# VSCard.net
KiCad netlist of a schematic drawn in EAGLE
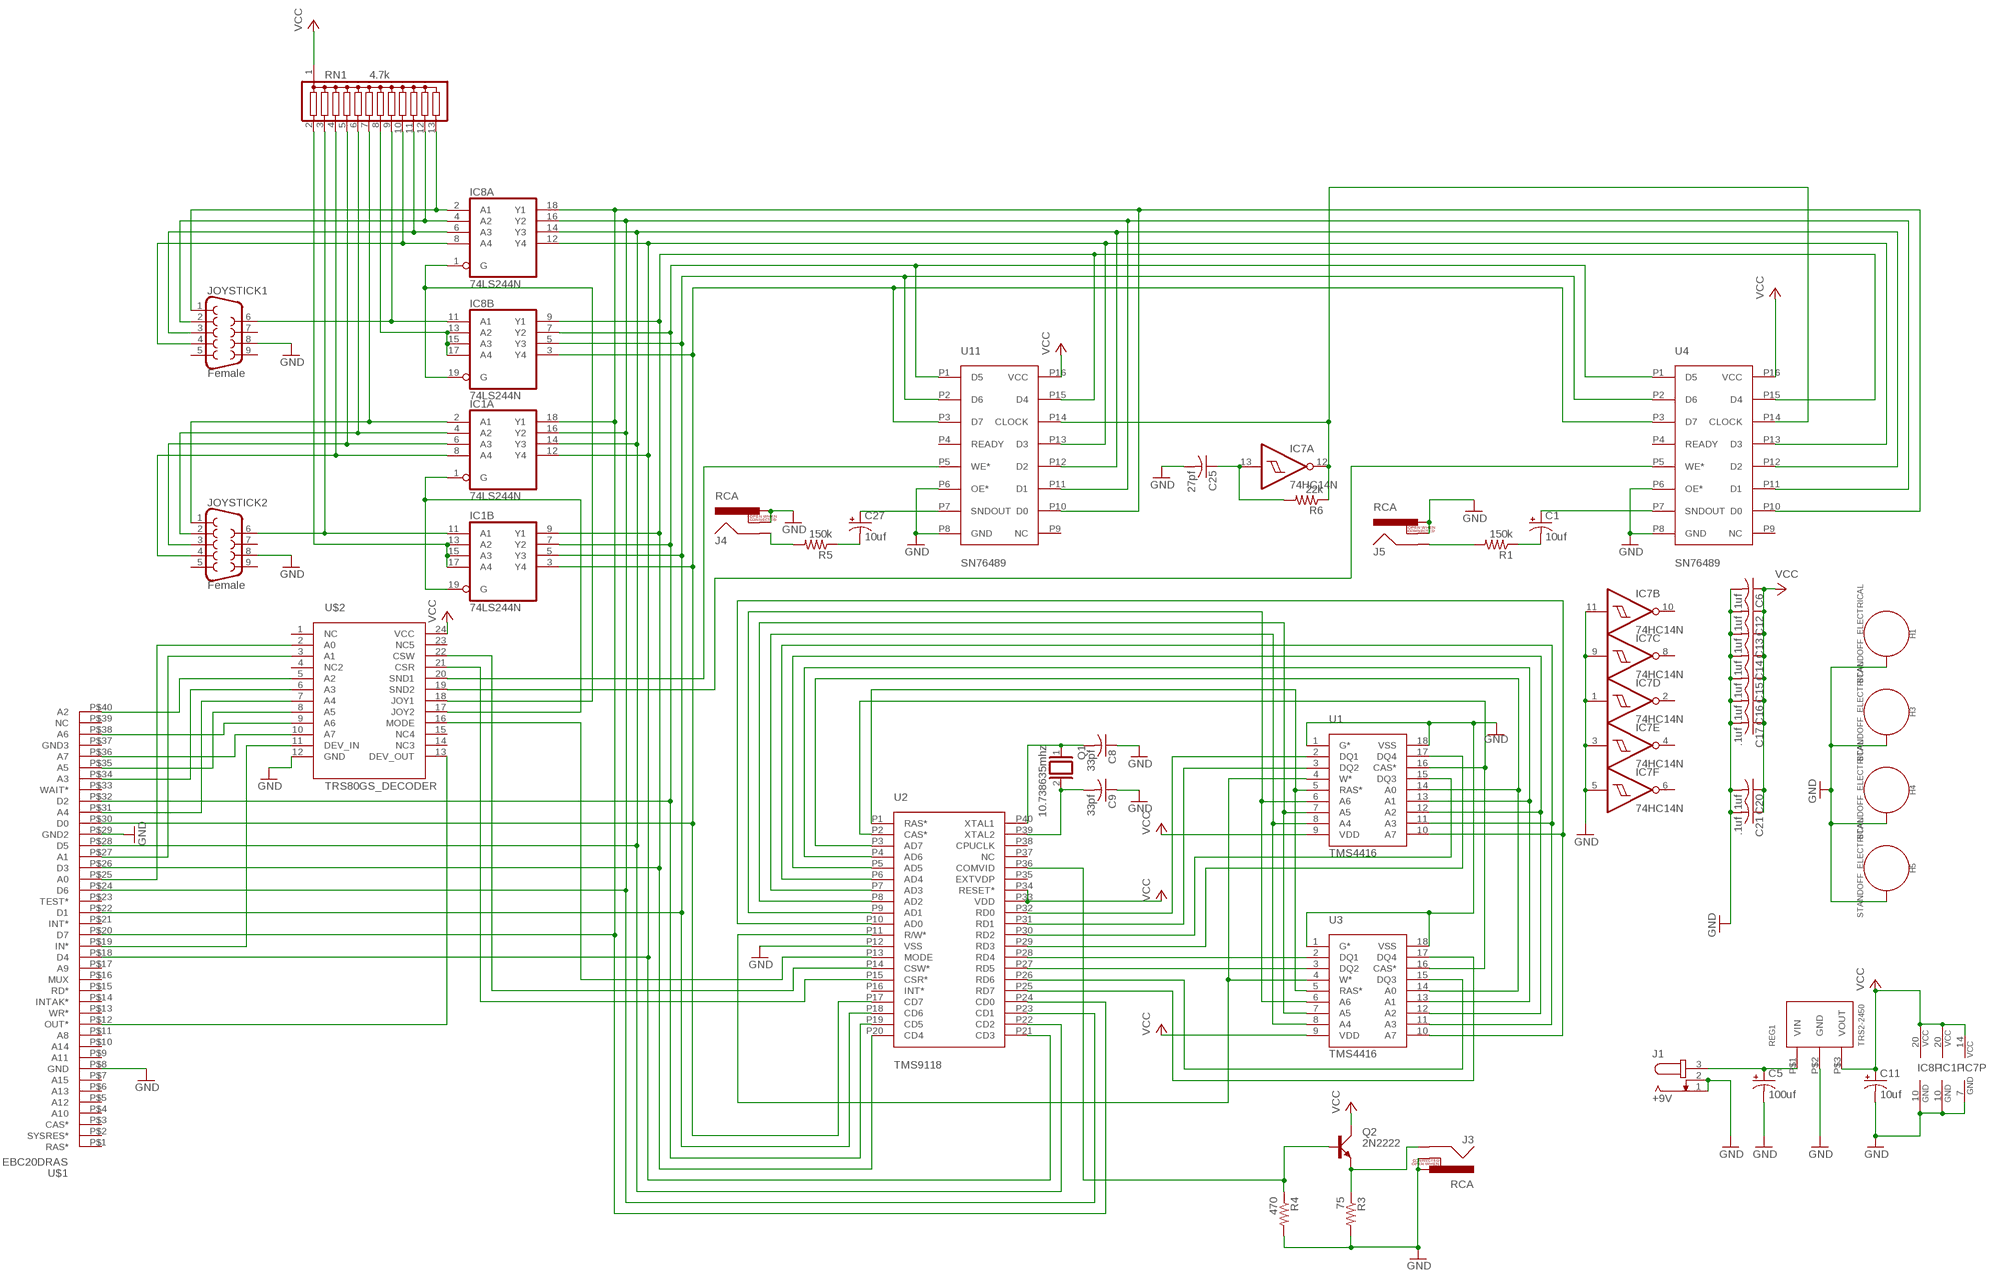
[diagram p0: schematic, sheet 1]

(export (version "E")
  (design (tool "Eeschema 10.0.6"))
  (components
    (comp (ref "C1")
      (value "10uf")
      (footprint "eagle-import:E2,5-6")
      (libsource (lib "eagle-import") (part "resistor_348_CPOL-USE2.5-6"))
    )
    (comp (ref "C5")
      (value "100uf")
      (footprint "eagle-import:E3,5-10")
      (libsource (lib "eagle-import") (part "CPOL-USE3.5-10"))
    )
    (comp (ref "C6")
      (value ".1uf")
      (footprint "eagle-import:C025-025X050")
      (libsource (lib "eagle-import") (part "resistor_348_C-US025-025X050"))
    )
    (comp (ref "C8")
      (value "33pf")
      (footprint "eagle-import:C050-050X075")
      (libsource (lib "eagle-import") (part "C-US050-050X075"))
    )
    (comp (ref "C9")
      (value "33pf")
      (footprint "eagle-import:C050-050X075")
      (libsource (lib "eagle-import") (part "C-US050-050X075"))
    )
    (comp (ref "C11")
      (value "10uf")
      (footprint "eagle-import:E3,5-10")
      (libsource (lib "eagle-import") (part "CPOL-USE3.5-10"))
    )
    (comp (ref "C12")
      (value ".1uf")
      (footprint "eagle-import:C025-025X050")
      (libsource (lib "eagle-import") (part "resistor_348_C-US025-025X050"))
    )
    (comp (ref "C13")
      (value ".1uf")
      (footprint "eagle-import:C025-025X050")
      (libsource (lib "eagle-import") (part "resistor_348_C-US025-025X050"))
    )
    (comp (ref "C14")
      (value ".1uf")
      (footprint "eagle-import:C025-025X050")
      (libsource (lib "eagle-import") (part "resistor_348_C-US025-025X050"))
    )
    (comp (ref "C15")
      (value ".1uf")
      (footprint "eagle-import:C025-025X050")
      (libsource (lib "eagle-import") (part "resistor_348_C-US025-025X050"))
    )
    (comp (ref "C16")
      (value ".1uf")
      (footprint "eagle-import:C025-025X050")
      (libsource (lib "eagle-import") (part "resistor_348_C-US025-025X050"))
    )
    (comp (ref "C17")
      (value ".1uf")
      (footprint "eagle-import:C025-025X050")
      (libsource (lib "eagle-import") (part "resistor_348_C-US025-025X050"))
    )
    (comp (ref "C20")
      (value ".1uf")
      (footprint "eagle-import:C025-025X050")
      (libsource (lib "eagle-import") (part "resistor_348_C-US025-025X050"))
    )
    (comp (ref "C21")
      (value ".1uf")
      (footprint "eagle-import:C025-025X050")
      (libsource (lib "eagle-import") (part "resistor_348_C-US025-025X050"))
    )
    (comp (ref "C25")
      (value "27pf")
      (footprint "eagle-import:C025-025X050")
      (libsource (lib "eagle-import") (part "resistor_348_C-US025-025X050"))
    )
    (comp (ref "C27")
      (value "10uf")
      (footprint "eagle-import:E2,5-6")
      (libsource (lib "eagle-import") (part "resistor_348_CPOL-USE2.5-6"))
    )
    (comp (ref "H1")
      (value "STANDOFF_ELECTRICAL")
      (footprint "eagle-import:STANDOFF-ELECTRICAL")
      (libsource (lib "eagle-import") (part "STANDOFF_ELECTRICAL"))
    )
    (comp (ref "H3")
      (value "STANDOFF_ELECTRICAL")
      (footprint "eagle-import:STANDOFF-ELECTRICAL")
      (libsource (lib "eagle-import") (part "STANDOFF_ELECTRICAL"))
    )
    (comp (ref "H4")
      (value "STANDOFF_ELECTRICAL")
      (footprint "eagle-import:STANDOFF-ELECTRICAL")
      (libsource (lib "eagle-import") (part "STANDOFF_ELECTRICAL"))
    )
    (comp (ref "H5")
      (value "STANDOFF_ELECTRICAL")
      (footprint "eagle-import:STANDOFF-ELECTRICAL")
      (libsource (lib "eagle-import") (part "STANDOFF_ELECTRICAL"))
    )
    (comp (ref "IC1")
      (value "74LS244N")
      (footprint "eagle-import:DIL20")
      (libsource (lib "eagle-import") (part "74244NLS"))
    )
    (comp (ref "IC7")
      (value "74HC14N")
      (footprint "eagle-import:DIL14")
      (libsource (lib "eagle-import") (part "7414NHC"))
    )
    (comp (ref "IC8")
      (value "74LS244N")
      (footprint "eagle-import:DIL20")
      (libsource (lib "eagle-import") (part "74244NLS"))
    )
    (comp (ref "J1")
      (value "+9V")
      (footprint "eagle-import:SPC4077")
      (libsource (lib "eagle-import") (part "JACK-PLUG0"))
    )
    (comp (ref "J3")
      (value "RCA")
      (footprint "eagle-import:RCA")
      (libsource (lib "eagle-import") (part "RCA"))
    )
    (comp (ref "J4")
      (value "RCA")
      (footprint "eagle-import:RCA")
      (libsource (lib "eagle-import") (part "RCA"))
    )
    (comp (ref "J5")
      (value "RCA")
      (footprint "eagle-import:RCA")
      (libsource (lib "eagle-import") (part "RCA"))
    )
    (comp (ref "JOYSTICK1")
      (value "Female")
      (footprint "eagle-import:DB9")
      (libsource (lib "eagle-import") (part "DB9FEMALE"))
    )
    (comp (ref "JOYSTICK2")
      (value "Female")
      (footprint "eagle-import:DB9")
      (libsource (lib "eagle-import") (part "DB9FEMALE"))
    )
    (comp (ref "Q1")
      (value "10.738635mhz")
      (footprint "eagle-import:QS")
      (libsource (lib "eagle-import") (part "XTAL/S"))
    )
    (comp (ref "Q2")
      (value "2N2222")
      (footprint "eagle-import:TO18A")
      (libsource (lib "eagle-import") (part "2N2222"))
    )
    (comp (ref "R1")
      (value "150k")
      (footprint "eagle-import:0207_2V")
      (libsource (lib "eagle-import") (part "R-US_0207/2V"))
    )
    (comp (ref "R3")
      (value "75")
      (footprint "eagle-import:0207_2V")
      (libsource (lib "eagle-import") (part "R-US_0207/2V"))
    )
    (comp (ref "R4")
      (value "470")
      (footprint "eagle-import:0207_2V")
      (libsource (lib "eagle-import") (part "R-US_0207/2V"))
    )
    (comp (ref "R5")
      (value "150k")
      (footprint "eagle-import:0207_2V")
      (libsource (lib "eagle-import") (part "R-US_0207/2V"))
    )
    (comp (ref "R6")
      (value "22k")
      (footprint "eagle-import:0207_2V")
      (libsource (lib "eagle-import") (part "R-US_0207/2V"))
    )
    (comp (ref "REG1")
      (value "TRS2-2450")
      (footprint "eagle-import:TRACON_REG")
      (libsource (lib "eagle-import") (part "TRS2-2450"))
    )
    (comp (ref "RN1")
      (value "4.7k")
      (footprint "eagle-import:SIL13")
      (libsource (lib "eagle-import") (part "G12R"))
    )
    (comp (ref "U$1")
      (value "EBC20DRAS")
      (footprint "eagle-import:EBC20DRAS")
      (libsource (lib "eagle-import") (part "EBC20DRAS"))
    )
    (comp (ref "U$2")
      (value "TRS80GS_DECODER")
      (footprint "eagle-import:DIP24SKI")
      (libsource (lib "eagle-import") (part "TRS80GS_DECODER"))
    )
    (comp (ref "U1")
      (value "TMS4416")
      (footprint "eagle-import:DIP18")
      (libsource (lib "eagle-import") (part "TMS4416"))
    )
    (comp (ref "U2")
      (value "TMS9118")
      (footprint "eagle-import:DIP40_MCU")
      (libsource (lib "eagle-import") (part "TMS9118"))
    )
    (comp (ref "U3")
      (value "TMS4416")
      (footprint "eagle-import:DIP18")
      (libsource (lib "eagle-import") (part "TMS4416"))
    )
    (comp (ref "U4")
      (value "SN76489")
      (footprint "eagle-import:DIP16")
      (libsource (lib "eagle-import") (part "SN76489"))
    )
    (comp (ref "U11")
      (value "SN76489")
      (footprint "eagle-import:DIP16")
      (libsource (lib "eagle-import") (part "SN76489"))
    )
  )
  (nets
    (net (code "1") (name "GND") (class "Default")
      (node (ref "C11") (pin "-") (pinfunction "-_-") (pintype "passive"))
      (node (ref "C12") (pin "2") (pinfunction "2_2") (pintype "passive"))
      (node (ref "C13") (pin "2") (pinfunction "2_2") (pintype "passive"))
      (node (ref "C14") (pin "2") (pinfunction "2_2") (pintype "passive"))
      (node (ref "C15") (pin "2") (pinfunction "2_2") (pintype "passive"))
      (node (ref "C16") (pin "2") (pinfunction "2_2") (pintype "passive"))
      (node (ref "C17") (pin "2") (pinfunction "2_2") (pintype "passive"))
      (node (ref "C20") (pin "2") (pinfunction "2_2") (pintype "passive"))
      (node (ref "C21") (pin "2") (pinfunction "2_2") (pintype "passive"))
      (node (ref "C25") (pin "2") (pinfunction "2_2") (pintype "passive"))
      (node (ref "C5") (pin "-") (pinfunction "-_-") (pintype "passive"))
      (node (ref "C6") (pin "2") (pinfunction "2_2") (pintype "passive"))
      (node (ref "C8") (pin "1") (pinfunction "1_1") (pintype "passive"))
      (node (ref "C9") (pin "1") (pinfunction "1_1") (pintype "passive"))
      (node (ref "H1") (pin "P1") (pinfunction "P$1_P1") (pintype "bidirectional"))
      (node (ref "H3") (pin "P1") (pinfunction "P$1_P1") (pintype "bidirectional"))
      (node (ref "H4") (pin "P1") (pinfunction "P$1_P1") (pintype "bidirectional"))
      (node (ref "H5") (pin "P1") (pinfunction "P$1_P1") (pintype "bidirectional"))
      (node (ref "IC1") (pin "10") (pinfunction "GND_10") (pintype "power_in"))
      (node (ref "IC7") (pin "1") (pinfunction "I_1") (pintype "input"))
      (node (ref "IC7") (pin "11") (pinfunction "I_11") (pintype "input"))
      (node (ref "IC7") (pin "3") (pinfunction "I_3") (pintype "input"))
      (node (ref "IC7") (pin "5") (pinfunction "I_5") (pintype "input"))
      (node (ref "IC7") (pin "7") (pinfunction "GND_7") (pintype "power_in"))
      (node (ref "IC7") (pin "9") (pinfunction "I_9") (pintype "input"))
      (node (ref "IC8") (pin "10") (pinfunction "GND_10") (pintype "power_in"))
      (node (ref "J1") (pin "1") (pinfunction "1_1") (pintype "passive"))
      (node (ref "J1") (pin "2") (pinfunction "2_2") (pintype "passive"))
      (node (ref "J3") (pin "PIN") (pinfunction "PIN_PIN") (pintype "bidirectional"))
      (node (ref "J3") (pin "SWITCH") (pinfunction "SWITCH_SWITCH") (pintype "bidirectional"))
      (node (ref "J4") (pin "PIN") (pinfunction "PIN_PIN") (pintype "bidirectional"))
      (node (ref "J4") (pin "SWITCH") (pinfunction "SWITCH_SWITCH") (pintype "bidirectional"))
      (node (ref "J5") (pin "PIN") (pinfunction "PIN_PIN") (pintype "bidirectional"))
      (node (ref "J5") (pin "SWITCH") (pinfunction "SWITCH_SWITCH") (pintype "bidirectional"))
      (node (ref "JOYSTICK1") (pin "8") (pinfunction "8_8") (pintype "passive"))
      (node (ref "JOYSTICK2") (pin "8") (pinfunction "8_8") (pintype "passive"))
      (node (ref "R3") (pin "2") (pinfunction "2_2") (pintype "passive"))
      (node (ref "R4") (pin "2") (pinfunction "2_2") (pintype "passive"))
      (node (ref "REG1") (pin "P$2") (pinfunction "GND_P$2") (pintype "bidirectional"))
      (node (ref "U$1") (pin "P$29") (pinfunction "GND2_P$29") (pintype "bidirectional"))
      (node (ref "U$1") (pin "P$8") (pinfunction "GND_P$8") (pintype "bidirectional"))
      (node (ref "U$2") (pin "12") (pinfunction "GND_12") (pintype "bidirectional"))
      (node (ref "U1") (pin "1") (pinfunction "G*_1") (pintype "bidirectional"))
      (node (ref "U1") (pin "18") (pinfunction "VSS_18") (pintype "bidirectional"))
      (node (ref "U11") (pin "P6") (pinfunction "OE*_P6") (pintype "bidirectional"))
      (node (ref "U11") (pin "P8") (pinfunction "GND_P8") (pintype "bidirectional"))
      (node (ref "U2") (pin "P12") (pinfunction "VSS_P12") (pintype "bidirectional"))
      (node (ref "U3") (pin "1") (pinfunction "G*_1") (pintype "bidirectional"))
      (node (ref "U3") (pin "18") (pinfunction "VSS_18") (pintype "bidirectional"))
      (node (ref "U4") (pin "P6") (pinfunction "OE*_P6") (pintype "bidirectional"))
      (node (ref "U4") (pin "P8") (pinfunction "GND_P8") (pintype "bidirectional"))
    )
    (net (code "2") (name "Net-(C1-Pad-)") (class "Default")
      (node (ref "C1") (pin "-") (pinfunction "-_-") (pintype "passive"))
      (node (ref "R1") (pin "1") (pinfunction "1_1") (pintype "passive"))
    )
    (net (code "3") (name "Net-(C27-Pad-)") (class "Default")
      (node (ref "C27") (pin "-") (pinfunction "-_-") (pintype "passive"))
      (node (ref "R5") (pin "1") (pinfunction "1_1") (pintype "passive"))
    )
    (net (code "4") (name "Net-(IC1A-A1)") (class "Default")
      (node (ref "IC1") (pin "2") (pinfunction "A1_2") (pintype "input"))
      (node (ref "JOYSTICK2") (pin "1") (pinfunction "1_1") (pintype "passive"))
      (node (ref "RN1") (pin "7") (pinfunction "7_7") (pintype "passive"))
    )
    (net (code "5") (name "Net-(IC1A-A2)") (class "Default")
      (node (ref "IC1") (pin "4") (pinfunction "A2_4") (pintype "input"))
      (node (ref "JOYSTICK2") (pin "2") (pinfunction "2_2") (pintype "passive"))
      (node (ref "RN1") (pin "6") (pinfunction "6_6") (pintype "passive"))
    )
    (net (code "6") (name "Net-(IC1A-A3)") (class "Default")
      (node (ref "IC1") (pin "6") (pinfunction "A3_6") (pintype "input"))
      (node (ref "JOYSTICK2") (pin "3") (pinfunction "3_3") (pintype "passive"))
      (node (ref "RN1") (pin "5") (pinfunction "5_5") (pintype "passive"))
    )
    (net (code "7") (name "Net-(IC1A-A4)") (class "Default")
      (node (ref "IC1") (pin "8") (pinfunction "A4_8") (pintype "input"))
      (node (ref "JOYSTICK2") (pin "4") (pinfunction "4_4") (pintype "passive"))
      (node (ref "RN1") (pin "4") (pinfunction "4_4") (pintype "passive"))
    )
    (net (code "8") (name "Net-(IC1A-G)") (class "Default")
      (node (ref "IC1") (pin "1") (pinfunction "G_1") (pintype "input"))
      (node (ref "IC1") (pin "19") (pinfunction "G_19") (pintype "input"))
      (node (ref "U$2") (pin "17") (pinfunction "JOY2_17") (pintype "bidirectional"))
    )
    (net (code "9") (name "Net-(IC1A-Y1)") (class "Default")
      (node (ref "IC1") (pin "18") (pinfunction "Y1_18") (pintype "tri_state"))
      (node (ref "IC8") (pin "18") (pinfunction "Y1_18") (pintype "tri_state"))
      (node (ref "U$1") (pin "P$20") (pinfunction "D7_P$20") (pintype "bidirectional"))
      (node (ref "U11") (pin "P10") (pinfunction "D0_P10") (pintype "bidirectional"))
      (node (ref "U2") (pin "P24") (pinfunction "CD0_P24") (pintype "bidirectional"))
      (node (ref "U4") (pin "P10") (pinfunction "D0_P10") (pintype "bidirectional"))
    )
    (net (code "10") (name "Net-(IC1A-Y2)") (class "Default")
      (node (ref "IC1") (pin "16") (pinfunction "Y2_16") (pintype "tri_state"))
      (node (ref "IC8") (pin "16") (pinfunction "Y2_16") (pintype "tri_state"))
      (node (ref "U$1") (pin "P$24") (pinfunction "D6_P$24") (pintype "bidirectional"))
      (node (ref "U11") (pin "P11") (pinfunction "D1_P11") (pintype "bidirectional"))
      (node (ref "U2") (pin "P23") (pinfunction "CD1_P23") (pintype "bidirectional"))
      (node (ref "U4") (pin "P11") (pinfunction "D1_P11") (pintype "bidirectional"))
    )
    (net (code "11") (name "Net-(IC1A-Y3)") (class "Default")
      (node (ref "IC1") (pin "14") (pinfunction "Y3_14") (pintype "tri_state"))
      (node (ref "IC8") (pin "14") (pinfunction "Y3_14") (pintype "tri_state"))
      (node (ref "U$1") (pin "P$28") (pinfunction "D5_P$28") (pintype "bidirectional"))
      (node (ref "U11") (pin "P12") (pinfunction "D2_P12") (pintype "bidirectional"))
      (node (ref "U2") (pin "P22") (pinfunction "CD2_P22") (pintype "bidirectional"))
      (node (ref "U4") (pin "P12") (pinfunction "D2_P12") (pintype "bidirectional"))
    )
    (net (code "12") (name "Net-(IC1A-Y4)") (class "Default")
      (node (ref "IC1") (pin "12") (pinfunction "Y4_12") (pintype "tri_state"))
      (node (ref "IC8") (pin "12") (pinfunction "Y4_12") (pintype "tri_state"))
      (node (ref "U$1") (pin "P$18") (pinfunction "D4_P$18") (pintype "bidirectional"))
      (node (ref "U11") (pin "P13") (pinfunction "D3_P13") (pintype "bidirectional"))
      (node (ref "U2") (pin "P21") (pinfunction "CD3_P21") (pintype "bidirectional"))
      (node (ref "U4") (pin "P13") (pinfunction "D3_P13") (pintype "bidirectional"))
    )
    (net (code "13") (name "Net-(IC1B-A1)") (class "Default")
      (node (ref "IC1") (pin "11") (pinfunction "A1_11") (pintype "input"))
      (node (ref "JOYSTICK2") (pin "6") (pinfunction "6_6") (pintype "passive"))
      (node (ref "RN1") (pin "3") (pinfunction "3_3") (pintype "passive"))
    )
    (net (code "14") (name "Net-(IC1B-A2)") (class "Default")
      (node (ref "IC1") (pin "13") (pinfunction "A2_13") (pintype "input"))
      (node (ref "IC1") (pin "15") (pinfunction "A3_15") (pintype "input"))
      (node (ref "IC1") (pin "17") (pinfunction "A4_17") (pintype "input"))
      (node (ref "RN1") (pin "2") (pinfunction "2_2") (pintype "passive"))
    )
    (net (code "15") (name "Net-(IC1B-Y1)") (class "Default")
      (node (ref "IC1") (pin "9") (pinfunction "Y1_9") (pintype "tri_state"))
      (node (ref "IC8") (pin "9") (pinfunction "Y1_9") (pintype "tri_state"))
      (node (ref "U$1") (pin "P$26") (pinfunction "D3_P$26") (pintype "bidirectional"))
      (node (ref "U11") (pin "P15") (pinfunction "D4_P15") (pintype "bidirectional"))
      (node (ref "U2") (pin "P20") (pinfunction "CD4_P20") (pintype "bidirectional"))
      (node (ref "U4") (pin "P15") (pinfunction "D4_P15") (pintype "bidirectional"))
    )
    (net (code "16") (name "Net-(IC1B-Y2)") (class "Default")
      (node (ref "IC1") (pin "7") (pinfunction "Y2_7") (pintype "tri_state"))
      (node (ref "IC8") (pin "7") (pinfunction "Y2_7") (pintype "tri_state"))
      (node (ref "U$1") (pin "P$32") (pinfunction "D2_P$32") (pintype "bidirectional"))
      (node (ref "U11") (pin "P1") (pinfunction "D5_P1") (pintype "bidirectional"))
      (node (ref "U2") (pin "P19") (pinfunction "CD5_P19") (pintype "bidirectional"))
      (node (ref "U4") (pin "P1") (pinfunction "D5_P1") (pintype "bidirectional"))
    )
    (net (code "17") (name "Net-(IC1B-Y3)") (class "Default")
      (node (ref "IC1") (pin "5") (pinfunction "Y3_5") (pintype "tri_state"))
      (node (ref "IC8") (pin "5") (pinfunction "Y3_5") (pintype "tri_state"))
      (node (ref "U$1") (pin "P$22") (pinfunction "D1_P$22") (pintype "bidirectional"))
      (node (ref "U11") (pin "P2") (pinfunction "D6_P2") (pintype "bidirectional"))
      (node (ref "U2") (pin "P18") (pinfunction "CD6_P18") (pintype "bidirectional"))
      (node (ref "U4") (pin "P2") (pinfunction "D6_P2") (pintype "bidirectional"))
    )
    (net (code "18") (name "Net-(IC1B-Y4)") (class "Default")
      (node (ref "IC1") (pin "3") (pinfunction "Y4_3") (pintype "tri_state"))
      (node (ref "IC8") (pin "3") (pinfunction "Y4_3") (pintype "tri_state"))
      (node (ref "U$1") (pin "P$30") (pinfunction "D0_P$30") (pintype "bidirectional"))
      (node (ref "U11") (pin "P3") (pinfunction "D7_P3") (pintype "bidirectional"))
      (node (ref "U2") (pin "P17") (pinfunction "CD7_P17") (pintype "bidirectional"))
      (node (ref "U4") (pin "P3") (pinfunction "D7_P3") (pintype "bidirectional"))
    )
    (net (code "19") (name "Net-(IC7A-I)") (class "Default")
      (node (ref "C25") (pin "1") (pinfunction "1_1") (pintype "passive"))
      (node (ref "IC7") (pin "13") (pinfunction "I_13") (pintype "input"))
      (node (ref "R6") (pin "2") (pinfunction "2_2") (pintype "passive"))
    )
    (net (code "20") (name "Net-(IC7A-O)") (class "Default")
      (node (ref "IC7") (pin "12") (pinfunction "O_12") (pintype "output"))
      (node (ref "R6") (pin "1") (pinfunction "1_1") (pintype "passive"))
      (node (ref "U11") (pin "P14") (pinfunction "CLOCK_P14") (pintype "bidirectional"))
      (node (ref "U4") (pin "P14") (pinfunction "CLOCK_P14") (pintype "bidirectional"))
    )
    (net (code "21") (name "Net-(IC8A-A1)") (class "Default")
      (node (ref "IC8") (pin "2") (pinfunction "A1_2") (pintype "input"))
      (node (ref "JOYSTICK1") (pin "1") (pinfunction "1_1") (pintype "passive"))
      (node (ref "RN1") (pin "13") (pinfunction "13_13") (pintype "passive"))
    )
    (net (code "22") (name "Net-(IC8A-A2)") (class "Default")
      (node (ref "IC8") (pin "4") (pinfunction "A2_4") (pintype "input"))
      (node (ref "JOYSTICK1") (pin "2") (pinfunction "2_2") (pintype "passive"))
      (node (ref "RN1") (pin "12") (pinfunction "12_12") (pintype "passive"))
    )
    (net (code "23") (name "Net-(IC8A-A3)") (class "Default")
      (node (ref "IC8") (pin "6") (pinfunction "A3_6") (pintype "input"))
      (node (ref "JOYSTICK1") (pin "3") (pinfunction "3_3") (pintype "passive"))
      (node (ref "RN1") (pin "11") (pinfunction "11_11") (pintype "passive"))
    )
    (net (code "24") (name "Net-(IC8A-A4)") (class "Default")
      (node (ref "IC8") (pin "8") (pinfunction "A4_8") (pintype "input"))
      (node (ref "JOYSTICK1") (pin "4") (pinfunction "4_4") (pintype "passive"))
      (node (ref "RN1") (pin "10") (pinfunction "10_10") (pintype "passive"))
    )
    (net (code "25") (name "Net-(IC8A-G)") (class "Default")
      (node (ref "IC8") (pin "1") (pinfunction "G_1") (pintype "input"))
      (node (ref "IC8") (pin "19") (pinfunction "G_19") (pintype "input"))
      (node (ref "U$2") (pin "18") (pinfunction "JOY1_18") (pintype "bidirectional"))
    )
    (net (code "26") (name "Net-(IC8B-A1)") (class "Default")
      (node (ref "IC8") (pin "11") (pinfunction "A1_11") (pintype "input"))
      (node (ref "JOYSTICK1") (pin "6") (pinfunction "6_6") (pintype "passive"))
      (node (ref "RN1") (pin "9") (pinfunction "9_9") (pintype "passive"))
    )
    (net (code "27") (name "Net-(IC8B-A2)") (class "Default")
      (node (ref "IC8") (pin "13") (pinfunction "A2_13") (pintype "input"))
      (node (ref "IC8") (pin "15") (pinfunction "A3_15") (pintype "input"))
      (node (ref "IC8") (pin "17") (pinfunction "A4_17") (pintype "input"))
      (node (ref "RN1") (pin "8") (pinfunction "8_8") (pintype "passive"))
    )
    (net (code "28") (name "Net-(J3-PadSHELL)") (class "Default")
      (node (ref "J3") (pin "SHELL") (pinfunction "SHELL_SHELL") (pintype "bidirectional"))
      (node (ref "Q2") (pin "E") (pinfunction "E_E") (pintype "passive"))
      (node (ref "R3") (pin "1") (pinfunction "1_1") (pintype "passive"))
    )
    (net (code "29") (name "Net-(J4-PadSHELL)") (class "Default")
      (node (ref "J4") (pin "SHELL") (pinfunction "SHELL_SHELL") (pintype "bidirectional"))
      (node (ref "R5") (pin "2") (pinfunction "2_2") (pintype "passive"))
    )
    (net (code "30") (name "Net-(J5-PadSHELL)") (class "Default")
      (node (ref "J5") (pin "SHELL") (pinfunction "SHELL_SHELL") (pintype "bidirectional"))
      (node (ref "R1") (pin "2") (pinfunction "2_2") (pintype "passive"))
    )
    (net (code "31") (name "Net-(REG1-VIN)") (class "Default")
      (node (ref "C5") (pin "+") (pinfunction "+_+") (pintype "passive"))
      (node (ref "J1") (pin "3") (pinfunction "3_3") (pintype "passive"))
      (node (ref "REG1") (pin "P$1") (pinfunction "VIN_P$1") (pintype "bidirectional"))
    )
    (net (code "32") (name "Net-(U$1-A0)") (class "Default")
      (node (ref "U$1") (pin "P$25") (pinfunction "A0_P$25") (pintype "bidirectional"))
      (node (ref "U$2") (pin "2") (pinfunction "A0_2") (pintype "bidirectional"))
    )
    (net (code "33") (name "Net-(U$1-A1)") (class "Default")
      (node (ref "U$1") (pin "P$27") (pinfunction "A1_P$27") (pintype "bidirectional"))
      (node (ref "U$2") (pin "3") (pinfunction "A1_3") (pintype "bidirectional"))
    )
    (net (code "34") (name "Net-(U$1-A2)") (class "Default")
      (node (ref "U$1") (pin "P$40") (pinfunction "A2_P$40") (pintype "bidirectional"))
      (node (ref "U$2") (pin "5") (pinfunction "A2_5") (pintype "bidirectional"))
    )
    (net (code "35") (name "Net-(U$1-A3)") (class "Default")
      (node (ref "U$1") (pin "P$34") (pinfunction "A3_P$34") (pintype "bidirectional"))
      (node (ref "U$2") (pin "6") (pinfunction "A3_6") (pintype "bidirectional"))
    )
    (net (code "36") (name "Net-(U$1-A4)") (class "Default")
      (node (ref "U$1") (pin "P$31") (pinfunction "A4_P$31") (pintype "bidirectional"))
      (node (ref "U$2") (pin "7") (pinfunction "A4_7") (pintype "bidirectional"))
    )
    (net (code "37") (name "Net-(U$1-A5)") (class "Default")
      (node (ref "U$1") (pin "P$35") (pinfunction "A5_P$35") (pintype "bidirectional"))
      (node (ref "U$2") (pin "8") (pinfunction "A5_8") (pintype "bidirectional"))
    )
    (net (code "38") (name "Net-(U$1-A6)") (class "Default")
      (node (ref "U$1") (pin "P$38") (pinfunction "A6_P$38") (pintype "bidirectional"))
      (node (ref "U$2") (pin "9") (pinfunction "A6_9") (pintype "bidirectional"))
    )
    (net (code "39") (name "Net-(U$1-A7)") (class "Default")
      (node (ref "U$1") (pin "P$36") (pinfunction "A7_P$36") (pintype "bidirectional"))
      (node (ref "U$2") (pin "10") (pinfunction "A7_10") (pintype "bidirectional"))
    )
    (net (code "40") (name "Net-(U$1-IN*)") (class "Default")
      (node (ref "U$1") (pin "P$19") (pinfunction "IN*_P$19") (pintype "bidirectional"))
      (node (ref "U$2") (pin "11") (pinfunction "DEV_IN_11") (pintype "bidirectional"))
    )
    (net (code "41") (name "Net-(U$1-OUT*)") (class "Default")
      (node (ref "U$1") (pin "P$12") (pinfunction "OUT*_P$12") (pintype "bidirectional"))
      (node (ref "U$2") (pin "13") (pinfunction "DEV_OUT_13") (pintype "bidirectional"))
    )
    (net (code "42") (name "Net-(U$2-CSR)") (class "Default")
      (node (ref "U$2") (pin "21") (pinfunction "CSR_21") (pintype "bidirectional"))
      (node (ref "U2") (pin "P15") (pinfunction "CSR*_P15") (pintype "bidirectional"))
    )
    (net (code "43") (name "Net-(U$2-CSW)") (class "Default")
      (node (ref "U$2") (pin "22") (pinfunction "CSW_22") (pintype "bidirectional"))
      (node (ref "U2") (pin "P14") (pinfunction "CSW*_P14") (pintype "bidirectional"))
    )
    (net (code "44") (name "Net-(U$2-MODE)") (class "Default")
      (node (ref "U$2") (pin "16") (pinfunction "MODE_16") (pintype "bidirectional"))
      (node (ref "U2") (pin "P13") (pinfunction "MODE_P13") (pintype "bidirectional"))
    )
    (net (code "45") (name "Net-(U$2-SND1)") (class "Default")
      (node (ref "U$2") (pin "20") (pinfunction "SND1_20") (pintype "bidirectional"))
      (node (ref "U11") (pin "P5") (pinfunction "WE*_P5") (pintype "bidirectional"))
    )
    (net (code "46") (name "Net-(U$2-SND2)") (class "Default")
      (node (ref "U$2") (pin "19") (pinfunction "SND2_19") (pintype "bidirectional"))
      (node (ref "U4") (pin "P5") (pinfunction "WE*_P5") (pintype "bidirectional"))
    )
    (net (code "47") (name "Net-(U1-A0)") (class "Default")
      (node (ref "U1") (pin "14") (pinfunction "A0_14") (pintype "bidirectional"))
      (node (ref "U2") (pin "P3") (pinfunction "AD7_P3") (pintype "bidirectional"))
      (node (ref "U3") (pin "14") (pinfunction "A0_14") (pintype "bidirectional"))
    )
    (net (code "48") (name "Net-(U1-A1)") (class "Default")
      (node (ref "U1") (pin "13") (pinfunction "A1_13") (pintype "bidirectional"))
      (node (ref "U2") (pin "P4") (pinfunction "AD6_P4") (pintype "bidirectional"))
      (node (ref "U3") (pin "13") (pinfunction "A1_13") (pintype "bidirectional"))
    )
    (net (code "49") (name "Net-(U1-A2)") (class "Default")
      (node (ref "U1") (pin "12") (pinfunction "A2_12") (pintype "bidirectional"))
      (node (ref "U2") (pin "P5") (pinfunction "AD5_P5") (pintype "bidirectional"))
      (node (ref "U3") (pin "12") (pinfunction "A2_12") (pintype "bidirectional"))
    )
    (net (code "50") (name "Net-(U1-A3)") (class "Default")
      (node (ref "U1") (pin "11") (pinfunction "A3_11") (pintype "bidirectional"))
      (node (ref "U2") (pin "P6") (pinfunction "AD4_P6") (pintype "bidirectional"))
      (node (ref "U3") (pin "11") (pinfunction "A3_11") (pintype "bidirectional"))
    )
    (net (code "51") (name "Net-(U1-A4)") (class "Default")
      (node (ref "U1") (pin "8") (pinfunction "A4_8") (pintype "bidirectional"))
      (node (ref "U2") (pin "P7") (pinfunction "AD3_P7") (pintype "bidirectional"))
      (node (ref "U3") (pin "8") (pinfunction "A4_8") (pintype "bidirectional"))
    )
    (net (code "52") (name "Net-(U1-A5)") (class "Default")
      (node (ref "U1") (pin "7") (pinfunction "A5_7") (pintype "bidirectional"))
      (node (ref "U2") (pin "P8") (pinfunction "AD2_P8") (pintype "bidirectional"))
      (node (ref "U3") (pin "7") (pinfunction "A5_7") (pintype "bidirectional"))
    )
    (net (code "53") (name "Net-(U1-A6)") (class "Default")
      (node (ref "U1") (pin "6") (pinfunction "A6_6") (pintype "bidirectional"))
      (node (ref "U2") (pin "P9") (pinfunction "AD1_P9") (pintype "bidirectional"))
      (node (ref "U3") (pin "6") (pinfunction "A6_6") (pintype "bidirectional"))
    )
    (net (code "54") (name "Net-(U1-A7)") (class "Default")
      (node (ref "U1") (pin "10") (pinfunction "A7_10") (pintype "bidirectional"))
      (node (ref "U2") (pin "P10") (pinfunction "AD0_P10") (pintype "bidirectional"))
      (node (ref "U3") (pin "10") (pinfunction "A7_10") (pintype "bidirectional"))
    )
    (net (code "55") (name "Net-(U1-CAS*)") (class "Default")
      (node (ref "U1") (pin "16") (pinfunction "CAS*_16") (pintype "bidirectional"))
      (node (ref "U2") (pin "P2") (pinfunction "CAS*_P2") (pintype "bidirectional"))
      (node (ref "U3") (pin "16") (pinfunction "CAS*_16") (pintype "bidirectional"))
    )
    (net (code "56") (name "Net-(U1-DQ1)") (class "Default")
      (node (ref "U1") (pin "2") (pinfunction "DQ1_2") (pintype "bidirectional"))
      (node (ref "U2") (pin "P32") (pinfunction "RD0_P32") (pintype "bidirectional"))
    )
    (net (code "57") (name "Net-(U1-DQ2)") (class "Default")
      (node (ref "U1") (pin "3") (pinfunction "DQ2_3") (pintype "bidirectional"))
      (node (ref "U2") (pin "P31") (pinfunction "RD1_P31") (pintype "bidirectional"))
    )
    (net (code "58") (name "Net-(U1-DQ3)") (class "Default")
      (node (ref "U1") (pin "15") (pinfunction "DQ3_15") (pintype "bidirectional"))
      (node (ref "U2") (pin "P30") (pinfunction "RD2_P30") (pintype "bidirectional"))
    )
    (net (code "59") (name "Net-(U1-DQ4)") (class "Default")
      (node (ref "U1") (pin "17") (pinfunction "DQ4_17") (pintype "bidirectional"))
      (node (ref "U2") (pin "P29") (pinfunction "RD3_P29") (pintype "bidirectional"))
    )
    (net (code "60") (name "Net-(U1-RAS*)") (class "Default")
      (node (ref "U1") (pin "5") (pinfunction "RAS*_5") (pintype "bidirectional"))
      (node (ref "U2") (pin "P1") (pinfunction "RAS*_P1") (pintype "bidirectional"))
      (node (ref "U3") (pin "5") (pinfunction "RAS*_5") (pintype "bidirectional"))
    )
    (net (code "61") (name "Net-(U1-W*)") (class "Default")
      (node (ref "U1") (pin "4") (pinfunction "W*_4") (pintype "bidirectional"))
      (node (ref "U2") (pin "P11") (pinfunction "R/W*_P11") (pintype "bidirectional"))
      (node (ref "U3") (pin "4") (pinfunction "W*_4") (pintype "bidirectional"))
    )
    (net (code "62") (name "Net-(U2-COMVID)") (class "Default")
      (node (ref "Q2") (pin "B") (pinfunction "B_B") (pintype "passive"))
      (node (ref "R4") (pin "1") (pinfunction "1_1") (pintype "passive"))
      (node (ref "U2") (pin "P36") (pinfunction "COMVID_P36") (pintype "bidirectional"))
    )
    (net (code "63") (name "Net-(U2-RD4)") (class "Default")
      (node (ref "U2") (pin "P28") (pinfunction "RD4_P28") (pintype "bidirectional"))
      (node (ref "U3") (pin "2") (pinfunction "DQ1_2") (pintype "bidirectional"))
    )
    (net (code "64") (name "Net-(U2-RD5)") (class "Default")
      (node (ref "U2") (pin "P27") (pinfunction "RD5_P27") (pintype "bidirectional"))
      (node (ref "U3") (pin "3") (pinfunction "DQ2_3") (pintype "bidirectional"))
    )
    (net (code "65") (name "Net-(U2-RD6)") (class "Default")
      (node (ref "U2") (pin "P26") (pinfunction "RD6_P26") (pintype "bidirectional"))
      (node (ref "U3") (pin "15") (pinfunction "DQ3_15") (pintype "bidirectional"))
    )
    (net (code "66") (name "Net-(U2-RD7)") (class "Default")
      (node (ref "U2") (pin "P25") (pinfunction "RD7_P25") (pintype "bidirectional"))
      (node (ref "U3") (pin "17") (pinfunction "DQ4_17") (pintype "bidirectional"))
    )
    (net (code "67") (name "Net-(U2-XTAL1)") (class "Default")
      (node (ref "C8") (pin "2") (pinfunction "2_2") (pintype "passive"))
      (node (ref "Q1") (pin "1") (pinfunction "1_1") (pintype "passive"))
      (node (ref "U2") (pin "P40") (pinfunction "XTAL1_P40") (pintype "bidirectional"))
    )
    (net (code "68") (name "Net-(U2-XTAL2)") (class "Default")
      (node (ref "C9") (pin "2") (pinfunction "2_2") (pintype "passive"))
      (node (ref "Q1") (pin "2") (pinfunction "2_2") (pintype "passive"))
      (node (ref "U2") (pin "P39") (pinfunction "XTAL2_P39") (pintype "bidirectional"))
    )
    (net (code "69") (name "Net-(U4-SNDOUT)") (class "Default")
      (node (ref "C1") (pin "+") (pinfunction "+_+") (pintype "passive"))
      (node (ref "U4") (pin "P7") (pinfunction "SNDOUT_P7") (pintype "bidirectional"))
    )
    (net (code "70") (name "Net-(U11-SNDOUT)") (class "Default")
      (node (ref "C27") (pin "+") (pinfunction "+_+") (pintype "passive"))
      (node (ref "U11") (pin "P7") (pinfunction "SNDOUT_P7") (pintype "bidirectional"))
    )
    (net (code "71") (name "VCC") (class "Default")
      (node (ref "C11") (pin "+") (pinfunction "+_+") (pintype "passive"))
      (node (ref "C12") (pin "1") (pinfunction "1_1") (pintype "passive"))
      (node (ref "C13") (pin "1") (pinfunction "1_1") (pintype "passive"))
      (node (ref "C14") (pin "1") (pinfunction "1_1") (pintype "passive"))
      (node (ref "C15") (pin "1") (pinfunction "1_1") (pintype "passive"))
      (node (ref "C16") (pin "1") (pinfunction "1_1") (pintype "passive"))
      (node (ref "C17") (pin "1") (pinfunction "1_1") (pintype "passive"))
      (node (ref "C20") (pin "1") (pinfunction "1_1") (pintype "passive"))
      (node (ref "C21") (pin "1") (pinfunction "1_1") (pintype "passive"))
      (node (ref "C6") (pin "1") (pinfunction "1_1") (pintype "passive"))
      (node (ref "IC1") (pin "20") (pinfunction "VCC_20") (pintype "power_in"))
      (node (ref "IC7") (pin "14") (pinfunction "VCC_14") (pintype "power_in"))
      (node (ref "IC8") (pin "20") (pinfunction "VCC_20") (pintype "power_in"))
      (node (ref "Q2") (pin "C") (pinfunction "C_C") (pintype "passive"))
      (node (ref "REG1") (pin "P$3") (pinfunction "VOUT_P$3") (pintype "bidirectional"))
      (node (ref "RN1") (pin "1") (pinfunction "1_1") (pintype "passive"))
      (node (ref "U$2") (pin "24") (pinfunction "VCC_24") (pintype "bidirectional"))
      (node (ref "U1") (pin "9") (pinfunction "VDD_9") (pintype "bidirectional"))
      (node (ref "U11") (pin "P16") (pinfunction "VCC_P16") (pintype "bidirectional"))
      (node (ref "U2") (pin "P33") (pinfunction "VDD_P33") (pintype "bidirectional"))
      (node (ref "U2") (pin "P34") (pinfunction "RESET*_P34") (pintype "bidirectional"))
      (node (ref "U3") (pin "9") (pinfunction "VDD_9") (pintype "bidirectional"))
      (node (ref "U4") (pin "P16") (pinfunction "VCC_P16") (pintype "bidirectional"))
    )
    (net (code "72") (name "unconnected-(IC7B-O-Pad10)") (class "Default")
      (node (ref "IC7") (pin "10") (pinfunction "O_10") (pintype "output"))
    )
    (net (code "73") (name "unconnected-(IC7C-O-Pad8)") (class "Default")
      (node (ref "IC7") (pin "8") (pinfunction "O_8") (pintype "output"))
    )
    (net (code "74") (name "unconnected-(IC7D-O-Pad2)") (class "Default")
      (node (ref "IC7") (pin "2") (pinfunction "O_2") (pintype "output"))
    )
    (net (code "75") (name "unconnected-(IC7E-O-Pad4)") (class "Default")
      (node (ref "IC7") (pin "4") (pinfunction "O_4") (pintype "output"))
    )
    (net (code "76") (name "unconnected-(IC7F-O-Pad6)") (class "Default")
      (node (ref "IC7") (pin "6") (pinfunction "O_6") (pintype "output"))
    )
    (net (code "77") (name "unconnected-(JOYSTICK1-Pad5)") (class "Default")
      (node (ref "JOYSTICK1") (pin "5") (pinfunction "5_5") (pintype "passive"))
    )
    (net (code "78") (name "unconnected-(JOYSTICK1-Pad7)") (class "Default")
      (node (ref "JOYSTICK1") (pin "7") (pinfunction "7_7") (pintype "passive"))
    )
    (net (code "79") (name "unconnected-(JOYSTICK1-Pad9)") (class "Default")
      (node (ref "JOYSTICK1") (pin "9") (pinfunction "9_9") (pintype "passive"))
    )
    (net (code "80") (name "unconnected-(JOYSTICK2-Pad5)") (class "Default")
      (node (ref "JOYSTICK2") (pin "5") (pinfunction "5_5") (pintype "passive"))
    )
    (net (code "81") (name "unconnected-(JOYSTICK2-Pad7)") (class "Default")
      (node (ref "JOYSTICK2") (pin "7") (pinfunction "7_7") (pintype "passive"))
    )
    (net (code "82") (name "unconnected-(JOYSTICK2-Pad9)") (class "Default")
      (node (ref "JOYSTICK2") (pin "9") (pinfunction "9_9") (pintype "passive"))
    )
    (net (code "83") (name "unconnected-(U$1-A8-PadP$11)") (class "Default")
      (node (ref "U$1") (pin "P$11") (pinfunction "A8_P$11") (pintype "bidirectional"))
    )
    (net (code "84") (name "unconnected-(U$1-A9-PadP$17)") (class "Default")
      (node (ref "U$1") (pin "P$17") (pinfunction "A9_P$17") (pintype "bidirectional"))
    )
    (net (code "85") (name "unconnected-(U$1-A10-PadP$4)") (class "Default")
      (node (ref "U$1") (pin "P$4") (pinfunction "A10_P$4") (pintype "bidirectional"))
    )
    (net (code "86") (name "unconnected-(U$1-A11-PadP$9)") (class "Default")
      (node (ref "U$1") (pin "P$9") (pinfunction "A11_P$9") (pintype "bidirectional"))
    )
    (net (code "87") (name "unconnected-(U$1-A12-PadP$5)") (class "Default")
      (node (ref "U$1") (pin "P$5") (pinfunction "A12_P$5") (pintype "bidirectional"))
    )
    (net (code "88") (name "unconnected-(U$1-A13-PadP$6)") (class "Default")
      (node (ref "U$1") (pin "P$6") (pinfunction "A13_P$6") (pintype "bidirectional"))
    )
    (net (code "89") (name "unconnected-(U$1-A14-PadP$10)") (class "Default")
      (node (ref "U$1") (pin "P$10") (pinfunction "A14_P$10") (pintype "bidirectional"))
    )
    (net (code "90") (name "unconnected-(U$1-A15-PadP$7)") (class "Default")
      (node (ref "U$1") (pin "P$7") (pinfunction "A15_P$7") (pintype "bidirectional"))
    )
    (net (code "91") (name "unconnected-(U$1-CAS*-PadP$3)") (class "Default")
      (node (ref "U$1") (pin "P$3") (pinfunction "CAS*_P$3") (pintype "bidirectional"))
    )
    (net (code "92") (name "unconnected-(U$1-GND3-PadP$37)") (class "Default")
      (node (ref "U$1") (pin "P$37") (pinfunction "GND3_P$37") (pintype "bidirectional"))
    )
    (net (code "93") (name "unconnected-(U$1-INT*-PadP$21)") (class "Default")
      (node (ref "U$1") (pin "P$21") (pinfunction "INT*_P$21") (pintype "bidirectional"))
    )
    (net (code "94") (name "unconnected-(U$1-INTAK*-PadP$14)") (class "Default")
      (node (ref "U$1") (pin "P$14") (pinfunction "INTAK*_P$14") (pintype "bidirectional"))
    )
    (net (code "95") (name "unconnected-(U$1-MUX-PadP$16)") (class "Default")
      (node (ref "U$1") (pin "P$16") (pinfunction "MUX_P$16") (pintype "bidirectional"))
    )
    (net (code "96") (name "unconnected-(U$1-NC-PadP$39)") (class "Default")
      (node (ref "U$1") (pin "P$39") (pinfunction "NC_P$39") (pintype "bidirectional"))
    )
    (net (code "97") (name "unconnected-(U$1-RAS*-PadP$1)") (class "Default")
      (node (ref "U$1") (pin "P$1") (pinfunction "RAS*_P$1") (pintype "bidirectional"))
    )
    (net (code "98") (name "unconnected-(U$1-RD*-PadP$15)") (class "Default")
      (node (ref "U$1") (pin "P$15") (pinfunction "RD*_P$15") (pintype "bidirectional"))
    )
    (net (code "99") (name "unconnected-(U$1-SYSRES*-PadP$2)") (class "Default")
      (node (ref "U$1") (pin "P$2") (pinfunction "SYSRES*_P$2") (pintype "bidirectional"))
    )
    (net (code "100") (name "unconnected-(U$1-TEST*-PadP$23)") (class "Default")
      (node (ref "U$1") (pin "P$23") (pinfunction "TEST*_P$23") (pintype "bidirectional"))
    )
    (net (code "101") (name "unconnected-(U$1-WAIT*-PadP$33)") (class "Default")
      (node (ref "U$1") (pin "P$33") (pinfunction "WAIT*_P$33") (pintype "bidirectional"))
    )
    (net (code "102") (name "unconnected-(U$1-WR*-PadP$13)") (class "Default")
      (node (ref "U$1") (pin "P$13") (pinfunction "WR*_P$13") (pintype "bidirectional"))
    )
    (net (code "103") (name "unconnected-(U$2-NC-Pad1)") (class "Default")
      (node (ref "U$2") (pin "1") (pinfunction "NC_1") (pintype "bidirectional"))
    )
    (net (code "104") (name "unconnected-(U$2-NC2-Pad4)") (class "Default")
      (node (ref "U$2") (pin "4") (pinfunction "NC2_4") (pintype "bidirectional"))
    )
    (net (code "105") (name "unconnected-(U$2-NC3-Pad14)") (class "Default")
      (node (ref "U$2") (pin "14") (pinfunction "NC3_14") (pintype "bidirectional"))
    )
    (net (code "106") (name "unconnected-(U$2-NC4-Pad15)") (class "Default")
      (node (ref "U$2") (pin "15") (pinfunction "NC4_15") (pintype "bidirectional"))
    )
    (net (code "107") (name "unconnected-(U$2-NC5-Pad23)") (class "Default")
      (node (ref "U$2") (pin "23") (pinfunction "NC5_23") (pintype "bidirectional"))
    )
    (net (code "108") (name "unconnected-(U2-CPUCLK-PadP38)") (class "Default")
      (node (ref "U2") (pin "P38") (pinfunction "CPUCLK_P38") (pintype "bidirectional"))
    )
    (net (code "109") (name "unconnected-(U2-EXTVDP-PadP35)") (class "Default")
      (node (ref "U2") (pin "P35") (pinfunction "EXTVDP_P35") (pintype "bidirectional"))
    )
    (net (code "110") (name "unconnected-(U2-INT*-PadP16)") (class "Default")
      (node (ref "U2") (pin "P16") (pinfunction "INT*_P16") (pintype "bidirectional"))
    )
    (net (code "111") (name "unconnected-(U2-NC-PadP37)") (class "Default")
      (node (ref "U2") (pin "P37") (pinfunction "NC_P37") (pintype "bidirectional"))
    )
    (net (code "112") (name "unconnected-(U4-NC-PadP9)") (class "Default")
      (node (ref "U4") (pin "P9") (pinfunction "NC_P9") (pintype "bidirectional"))
    )
    (net (code "113") (name "unconnected-(U4-READY-PadP4)") (class "Default")
      (node (ref "U4") (pin "P4") (pinfunction "READY_P4") (pintype "bidirectional"))
    )
    (net (code "114") (name "unconnected-(U11-NC-PadP9)") (class "Default")
      (node (ref "U11") (pin "P9") (pinfunction "NC_P9") (pintype "bidirectional"))
    )
    (net (code "115") (name "unconnected-(U11-READY-PadP4)") (class "Default")
      (node (ref "U11") (pin "P4") (pinfunction "READY_P4") (pintype "bidirectional"))
    )
  )
)
